# Sheet.net
KiCad netlist of a schematic drawn in Altium Designer
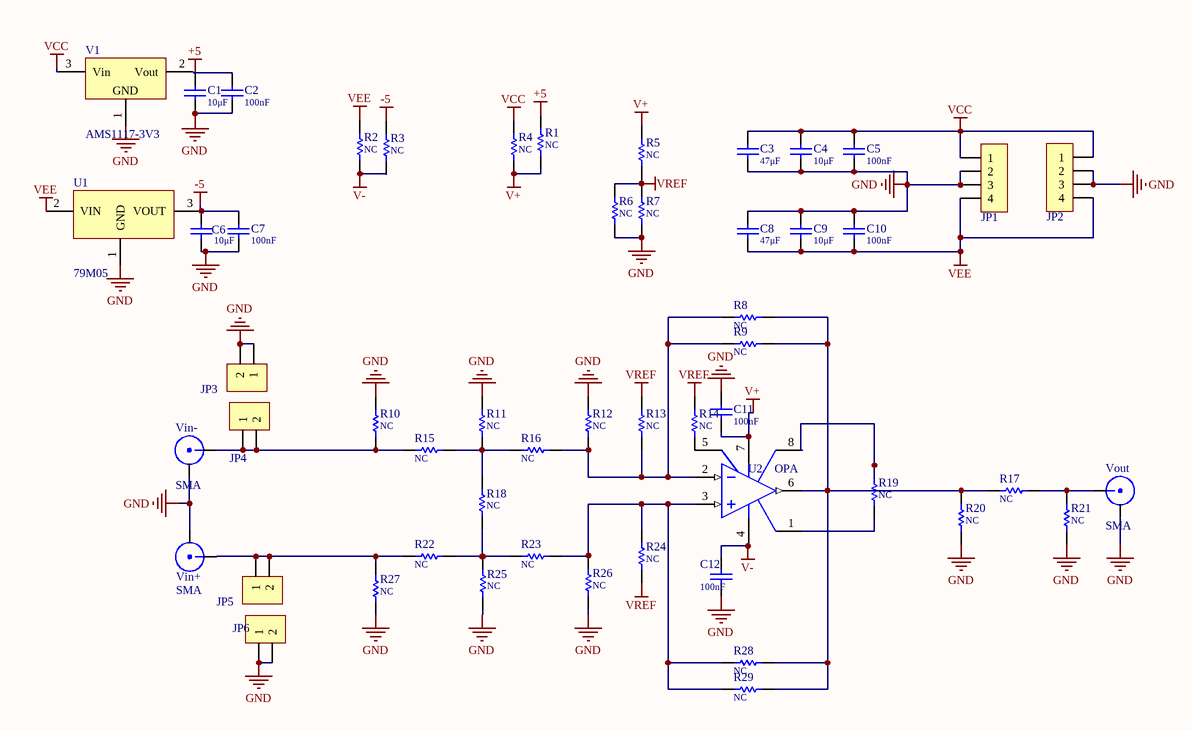
[diagram p0: Sheet.SchDoc]

(export (version "E")
  (design (tool "Eeschema 10.0.6"))
  (components
    (comp (ref "C1")
      (value "10μF")
      (footprint "C0805-L")
      (description "贴片瓷片电容")
      (fields (field (name "Comment") "Cap-S"))
      (libsource (lib "Library") (part "Cap-S"))
    )
    (comp (ref "C2")
      (value "100nF")
      (footprint "C0603-L")
      (description "贴片瓷片电容")
      (fields (field (name "Comment") "Cap-S"))
      (libsource (lib "Library") (part "Cap-S"))
    )
    (comp (ref "C3")
      (value "47μF")
      (footprint "C0805-L")
      (description "贴片瓷片电容")
      (fields (field (name "Comment") "Cap-S"))
      (libsource (lib "Library") (part "Cap-S"))
    )
    (comp (ref "C4")
      (value "10μF")
      (footprint "C0805-L")
      (description "贴片瓷片电容")
      (fields (field (name "Comment") "Cap-S"))
      (libsource (lib "Library") (part "Cap-S"))
    )
    (comp (ref "C5")
      (value "100nF")
      (footprint "C0603-L")
      (description "贴片瓷片电容")
      (fields (field (name "Comment") "Cap-S"))
      (libsource (lib "Library") (part "Cap-S"))
    )
    (comp (ref "C6")
      (value "10μF")
      (footprint "C0805-L")
      (description "贴片瓷片电容")
      (fields (field (name "Comment") "Cap-S"))
      (libsource (lib "Library") (part "Cap-S"))
    )
    (comp (ref "C7")
      (value "100nF")
      (footprint "C0603-L")
      (description "贴片瓷片电容")
      (fields (field (name "Comment") "Cap-S"))
      (libsource (lib "Library") (part "Cap-S"))
    )
    (comp (ref "C8")
      (value "47μF")
      (footprint "C0805-L")
      (description "贴片瓷片电容")
      (fields (field (name "Comment") "Cap-S"))
      (libsource (lib "Library") (part "Cap-S"))
    )
    (comp (ref "C9")
      (value "10μF")
      (footprint "C0805-L")
      (description "贴片瓷片电容")
      (fields (field (name "Comment") "Cap-S"))
      (libsource (lib "Library") (part "Cap-S"))
    )
    (comp (ref "C10")
      (value "100nF")
      (footprint "C0603-L")
      (description "贴片瓷片电容")
      (fields (field (name "Comment") "Cap-S"))
      (libsource (lib "Library") (part "Cap-S"))
    )
    (comp (ref "C11")
      (value "100nF")
      (footprint "C0603-L")
      (description "贴片瓷片电容")
      (fields (field (name "Comment") "Cap-S"))
      (libsource (lib "Library") (part "Cap-S"))
    )
    (comp (ref "C12")
      (value "100nF")
      (footprint "C0603-L")
      (description "贴片瓷片电容")
      (fields (field (name "Comment") "Cap-S"))
      (libsource (lib "Library") (part "Cap-S"))
    )
    (comp (ref "JP1")
      (value "HDR-1X4")
      (footprint "VH3.96-LI-4P")
      (description "4P接插件")
      (fields (field (name "版权归属") "源创客"))
      (libsource (lib "") (part "Header 4_1"))
    )
    (comp (ref "JP2")
      (value "HDR-1X4")
      (footprint "VH3.96-LI-4P")
      (description "4P接插件")
      (fields (field (name "版权归属") "源创客"))
      (libsource (lib "Library1") (part "Header 4"))
    )
    (comp (ref "JP3")
      (value "HDR-1X2")
      (footprint "HDR2.54-LI-2P")
      (description "2P接插件")
      (fields (field (name "版权归属") "源创客"))
      (libsource (lib "IL") (part "Header 2"))
    )
    (comp (ref "JP4")
      (value "HDR-1X2")
      (footprint "HDR2.54-LI-2P")
      (description "2P接插件")
      (fields (field (name "版权归属") "源创客"))
      (libsource (lib "") (part "Header 2_1"))
    )
    (comp (ref "JP5")
      (value "HDR-1X2")
      (footprint "HDR2.54-LI-2P")
      (description "2P接插件")
      (fields (field (name "版权归属") "源创客"))
      (libsource (lib "") (part "Header 2_2"))
    )
    (comp (ref "JP6")
      (value "HDR-1X2")
      (footprint "HDR2.54-LI-2P")
      (description "2P接插件")
      (fields (field (name "版权归属") "源创客"))
      (libsource (lib "") (part "Header 2_1"))
    )
    (comp (ref "R1")
      (value "NC")
      (footprint "R0603-L")
      (description "贴片电阻")
      (fields (field (name "Comment") "R"))
      (libsource (lib "Library") (part "Res"))
    )
    (comp (ref "R2")
      (value "NC")
      (footprint "R0603-L")
      (description "贴片电阻")
      (fields (field (name "Comment") "R"))
      (libsource (lib "Library") (part "Res"))
    )
    (comp (ref "R3")
      (value "NC")
      (footprint "R0603-L")
      (description "贴片电阻")
      (fields (field (name "Comment") "R"))
      (libsource (lib "Library") (part "Res"))
    )
    (comp (ref "R4")
      (value "NC")
      (footprint "R0603-L")
      (description "贴片电阻")
      (fields (field (name "Comment") "R"))
      (libsource (lib "Library") (part "Res"))
    )
    (comp (ref "R5")
      (value "NC")
      (footprint "R0603-L")
      (description "贴片电阻")
      (fields (field (name "Comment") "R"))
      (libsource (lib "Library") (part "Res"))
    )
    (comp (ref "R6")
      (value "NC")
      (footprint "R0603-L")
      (description "贴片电阻")
      (fields (field (name "Comment") "R"))
      (libsource (lib "Library") (part "Res"))
    )
    (comp (ref "R7")
      (value "NC")
      (footprint "R0603-L")
      (description "贴片电阻")
      (fields (field (name "Comment") "R"))
      (libsource (lib "Library") (part "Res"))
    )
    (comp (ref "R8")
      (value "NC")
      (footprint "R0603-L")
      (description "贴片电阻")
      (fields (field (name "Comment") "R"))
      (libsource (lib "Library") (part "Res"))
    )
    (comp (ref "R9")
      (value "NC")
      (footprint "R0603-L")
      (description "贴片电阻")
      (fields (field (name "Comment") "R"))
      (libsource (lib "Library") (part "Res"))
    )
    (comp (ref "R10")
      (value "NC")
      (footprint "R0603-L")
      (description "贴片电阻")
      (fields (field (name "Comment") "R"))
      (libsource (lib "Library") (part "Res"))
    )
    (comp (ref "R11")
      (value "NC")
      (footprint "R0603-L")
      (description "贴片电阻")
      (fields (field (name "Comment") "R"))
      (libsource (lib "Library") (part "Res"))
    )
    (comp (ref "R12")
      (value "NC")
      (footprint "R0603-L")
      (description "贴片电阻")
      (fields (field (name "Comment") "R"))
      (libsource (lib "Library") (part "Res"))
    )
    (comp (ref "R13")
      (value "NC")
      (footprint "R0603-L")
      (description "贴片电阻")
      (fields (field (name "Comment") "R"))
      (libsource (lib "Library") (part "Res"))
    )
    (comp (ref "R14")
      (value "NC")
      (footprint "R0603-L")
      (description "贴片电阻")
      (fields (field (name "Comment") "R"))
      (libsource (lib "Library") (part "Res"))
    )
    (comp (ref "R15")
      (value "NC")
      (footprint "R0603-L")
      (description "贴片电阻")
      (fields (field (name "Comment") "R"))
      (libsource (lib "Library") (part "Res"))
    )
    (comp (ref "R16")
      (value "NC")
      (footprint "R0603-L")
      (description "贴片电阻")
      (fields (field (name "Comment") "R"))
      (libsource (lib "Library") (part "Res"))
    )
    (comp (ref "R17")
      (value "NC")
      (footprint "R0603-L")
      (description "贴片电阻")
      (fields (field (name "Comment") "R"))
      (libsource (lib "Library") (part "Res"))
    )
    (comp (ref "R18")
      (value "NC")
      (footprint "R0603-L")
      (description "贴片电阻")
      (fields (field (name "Comment") "R"))
      (libsource (lib "Library") (part "Res"))
    )
    (comp (ref "R19")
      (value "NC")
      (footprint "R0603-L")
      (description "贴片电阻")
      (fields (field (name "Comment") "R"))
      (libsource (lib "Library") (part "Res"))
    )
    (comp (ref "R20")
      (value "NC")
      (footprint "R0603-L")
      (description "贴片电阻")
      (fields (field (name "Comment") "R"))
      (libsource (lib "Library") (part "Res"))
    )
    (comp (ref "R21")
      (value "NC")
      (footprint "R0603-L")
      (description "贴片电阻")
      (fields (field (name "Comment") "R"))
      (libsource (lib "Library") (part "Res"))
    )
    (comp (ref "R22")
      (value "NC")
      (footprint "R0603-L")
      (description "贴片电阻")
      (fields (field (name "Comment") "R"))
      (libsource (lib "Library") (part "Res"))
    )
    (comp (ref "R23")
      (value "NC")
      (footprint "R0603-L")
      (description "贴片电阻")
      (fields (field (name "Comment") "R"))
      (libsource (lib "Library") (part "Res"))
    )
    (comp (ref "R24")
      (value "NC")
      (footprint "R0603-L")
      (description "贴片电阻")
      (fields (field (name "Comment") "R"))
      (libsource (lib "Library") (part "Res"))
    )
    (comp (ref "R25")
      (value "NC")
      (footprint "R0603-L")
      (description "贴片电阻")
      (fields (field (name "Comment") "R"))
      (libsource (lib "Library") (part "Res"))
    )
    (comp (ref "R26")
      (value "NC")
      (footprint "R0603-L")
      (description "贴片电阻")
      (fields (field (name "Comment") "R"))
      (libsource (lib "Library") (part "Res"))
    )
    (comp (ref "R27")
      (value "NC")
      (footprint "R0603-L")
      (description "贴片电阻")
      (fields (field (name "Comment") "R"))
      (libsource (lib "Library") (part "Res"))
    )
    (comp (ref "R28")
      (value "NC")
      (footprint "R0603-L")
      (description "贴片电阻")
      (fields (field (name "Comment") "R"))
      (libsource (lib "Library") (part "Res"))
    )
    (comp (ref "R29")
      (value "NC")
      (footprint "R0603-L")
      (description "贴片电阻")
      (fields (field (name "Comment") "R"))
      (libsource (lib "Library") (part "Res"))
    )
    (comp (ref "U1")
      (value "79M05")
      (footprint "TO252")
      (description "线性稳压芯片")
      (fields (field (name "版权归属") "源创客"))
      (libsource (lib "IL") (part "79xx"))
    )
    (comp (ref "U2")
      (value "OPA")
      (footprint "SOP8_N")
      (description "双电源高精度运放")
      (fields (field (name "版权归属") "源创客"))
      (libsource (lib "Library1") (part "OPA277"))
    )
    (comp (ref "V1")
      (value "AMS1117-3V3")
      (footprint "SOT223_L")
      (description "三端稳压芯片")
      (fields (field (name "版权归属") "源创客"))
      (libsource (lib "IL") (part "AMS1117"))
    )
    (comp (ref "Vin+") (value "SMA") (footprint "SMA1") (libsource (lib "Library") (part "SMA")))
    (comp (ref "Vin-") (value "SMA") (footprint "SMA1") (libsource (lib "") (part "SMA_1")))
    (comp (ref "Vout") (value "SMA") (footprint "SMA1") (libsource (lib "Library") (part "SMA")))
  )
  (nets
    (net (code "1") (name "+5") (class "Default")
      (node (ref "C1") (pin "2") (pinfunction "2_2") (pintype "passive"))
      (node (ref "C2") (pin "2") (pinfunction "2_2") (pintype "passive"))
      (node (ref "R1") (pin "1") (pinfunction "1_1") (pintype "passive"))
      (node (ref "V1") (pin "2") (pinfunction "Vout_2") (pintype "passive"))
    )
    (net (code "2") (name "-5") (class "Default")
      (node (ref "C6") (pin "2") (pinfunction "2_2") (pintype "passive"))
      (node (ref "C7") (pin "2") (pinfunction "2_2") (pintype "passive"))
      (node (ref "R3") (pin "1") (pinfunction "1_1") (pintype "passive"))
      (node (ref "U1") (pin "3") (pinfunction "VOUT_3") (pintype "passive"))
    )
    (net (code "3") (name "GND") (class "Default")
      (node (ref "C1") (pin "1") (pinfunction "1_1") (pintype "passive"))
      (node (ref "C10") (pin "2") (pinfunction "2_2") (pintype "passive"))
      (node (ref "C11") (pin "2") (pinfunction "2_2") (pintype "passive"))
      (node (ref "C12") (pin "1") (pinfunction "1_1") (pintype "passive"))
      (node (ref "C2") (pin "1") (pinfunction "1_1") (pintype "passive"))
      (node (ref "C3") (pin "1") (pinfunction "1_1") (pintype "passive"))
      (node (ref "C4") (pin "1") (pinfunction "1_1") (pintype "passive"))
      (node (ref "C5") (pin "1") (pinfunction "1_1") (pintype "passive"))
      (node (ref "C6") (pin "1") (pinfunction "1_1") (pintype "passive"))
      (node (ref "C7") (pin "1") (pinfunction "1_1") (pintype "passive"))
      (node (ref "C8") (pin "2") (pinfunction "2_2") (pintype "passive"))
      (node (ref "C9") (pin "2") (pinfunction "2_2") (pintype "passive"))
      (node (ref "JP1") (pin "2") (pinfunction "2_2") (pintype "passive"))
      (node (ref "JP1") (pin "3") (pinfunction "3_3") (pintype "passive"))
      (node (ref "JP2") (pin "2") (pinfunction "2_2") (pintype "passive"))
      (node (ref "JP2") (pin "3") (pinfunction "3_3") (pintype "passive"))
      (node (ref "JP3") (pin "1") (pinfunction "1_1") (pintype "passive"))
      (node (ref "JP3") (pin "2") (pinfunction "2_2") (pintype "passive"))
      (node (ref "JP6") (pin "1") (pinfunction "1_1") (pintype "passive"))
      (node (ref "JP6") (pin "2") (pinfunction "2_2") (pintype "passive"))
      (node (ref "R10") (pin "2") (pinfunction "2_2") (pintype "passive"))
      (node (ref "R11") (pin "2") (pinfunction "2_2") (pintype "passive"))
      (node (ref "R12") (pin "2") (pinfunction "2_2") (pintype "passive"))
      (node (ref "R20") (pin "1") (pinfunction "1_1") (pintype "passive"))
      (node (ref "R21") (pin "1") (pinfunction "1_1") (pintype "passive"))
      (node (ref "R25") (pin "1") (pinfunction "1_1") (pintype "passive"))
      (node (ref "R26") (pin "1") (pinfunction "1_1") (pintype "passive"))
      (node (ref "R27") (pin "1") (pinfunction "1_1") (pintype "passive"))
      (node (ref "R6") (pin "2") (pinfunction "2_2") (pintype "passive"))
      (node (ref "R7") (pin "2") (pinfunction "2_2") (pintype "passive"))
      (node (ref "U1") (pin "1") (pinfunction "GND_1") (pintype "passive"))
      (node (ref "V1") (pin "1") (pinfunction "GND_1") (pintype "passive"))
      (node (ref "Vin+") (pin "2") (pinfunction "2_2") (pintype "passive"))
      (node (ref "Vin-") (pin "2") (pinfunction "2_2") (pintype "passive"))
      (node (ref "Vout") (pin "2") (pinfunction "2_2") (pintype "passive"))
    )
    (net (code "4") (name "Net-(JP4-Pad1)") (class "Default")
      (node (ref "JP4") (pin "1") (pinfunction "1_1") (pintype "passive"))
      (node (ref "JP4") (pin "2") (pinfunction "2_2") (pintype "passive"))
      (node (ref "R10") (pin "1") (pinfunction "1_1") (pintype "passive"))
      (node (ref "R15") (pin "1") (pinfunction "1_1") (pintype "passive"))
      (node (ref "Vin-") (pin "1") (pinfunction "1_1") (pintype "passive"))
    )
    (net (code "5") (name "Net-(JP5-Pad1)") (class "Default")
      (node (ref "JP5") (pin "1") (pinfunction "1_1") (pintype "passive"))
      (node (ref "JP5") (pin "2") (pinfunction "2_2") (pintype "passive"))
      (node (ref "R22") (pin "1") (pinfunction "1_1") (pintype "passive"))
      (node (ref "R27") (pin "2") (pinfunction "2_2") (pintype "passive"))
      (node (ref "Vin+") (pin "1") (pinfunction "1_1") (pintype "passive"))
    )
    (net (code "6") (name "Net-(R11-Pad1)") (class "Default")
      (node (ref "R11") (pin "1") (pinfunction "1_1") (pintype "passive"))
      (node (ref "R15") (pin "2") (pinfunction "2_2") (pintype "passive"))
      (node (ref "R16") (pin "1") (pinfunction "1_1") (pintype "passive"))
      (node (ref "R18") (pin "1") (pinfunction "1_1") (pintype "passive"))
    )
    (net (code "7") (name "Net-(R17-Pad2)") (class "Default")
      (node (ref "R17") (pin "2") (pinfunction "2_2") (pintype "passive"))
      (node (ref "R21") (pin "2") (pinfunction "2_2") (pintype "passive"))
      (node (ref "Vout") (pin "1") (pinfunction "1_1") (pintype "passive"))
    )
    (net (code "8") (name "Net-(R18-Pad2)") (class "Default")
      (node (ref "R18") (pin "2") (pinfunction "2_2") (pintype "passive"))
      (node (ref "R22") (pin "2") (pinfunction "2_2") (pintype "passive"))
      (node (ref "R23") (pin "1") (pinfunction "1_1") (pintype "passive"))
      (node (ref "R25") (pin "2") (pinfunction "2_2") (pintype "passive"))
    )
    (net (code "9") (name "Net-(R19-Pad1)") (class "Default")
      (node (ref "R19") (pin "1") (pinfunction "1_1") (pintype "passive"))
      (node (ref "U2") (pin "8") (pinfunction "8_8") (pintype "passive"))
    )
    (net (code "10") (name "Net-(R19-Pad2)") (class "Default")
      (node (ref "R19") (pin "2") (pinfunction "2_2") (pintype "passive"))
      (node (ref "U2") (pin "1") (pinfunction "1_1") (pintype "passive"))
    )
    (net (code "11") (name "Net-(U2-IN+)") (class "Default")
      (node (ref "R23") (pin "2") (pinfunction "2_2") (pintype "passive"))
      (node (ref "R24") (pin "2") (pinfunction "2_2") (pintype "passive"))
      (node (ref "R26") (pin "2") (pinfunction "2_2") (pintype "passive"))
      (node (ref "R28") (pin "1") (pinfunction "1_1") (pintype "passive"))
      (node (ref "R29") (pin "1") (pinfunction "1_1") (pintype "passive"))
      (node (ref "U2") (pin "3") (pinfunction "IN+_3") (pintype "input"))
    )
    (net (code "12") (name "Net-(U2-IN-)") (class "Default")
      (node (ref "R12") (pin "1") (pinfunction "1_1") (pintype "passive"))
      (node (ref "R13") (pin "1") (pinfunction "1_1") (pintype "passive"))
      (node (ref "R16") (pin "2") (pinfunction "2_2") (pintype "passive"))
      (node (ref "R8") (pin "1") (pinfunction "1_1") (pintype "passive"))
      (node (ref "R9") (pin "1") (pinfunction "1_1") (pintype "passive"))
      (node (ref "U2") (pin "2") (pinfunction "IN-_2") (pintype "input"))
    )
    (net (code "13") (name "Net-(U2-NC)") (class "Default")
      (node (ref "R14") (pin "1") (pinfunction "1_1") (pintype "passive"))
      (node (ref "U2") (pin "5") (pinfunction "NC_5") (pintype "power_in"))
    )
    (net (code "14") (name "Net-(U2-OS_NUL)") (class "Default")
      (node (ref "R17") (pin "1") (pinfunction "1_1") (pintype "passive"))
      (node (ref "R20") (pin "2") (pinfunction "2_2") (pintype "passive"))
      (node (ref "R28") (pin "2") (pinfunction "2_2") (pintype "passive"))
      (node (ref "R29") (pin "2") (pinfunction "2_2") (pintype "passive"))
      (node (ref "R8") (pin "2") (pinfunction "2_2") (pintype "passive"))
      (node (ref "R9") (pin "2") (pinfunction "2_2") (pintype "passive"))
      (node (ref "U2") (pin "6") (pinfunction "OS_NUL_6") (pintype "output"))
    )
    (net (code "15") (name "V+") (class "Default")
      (node (ref "C11") (pin "1") (pinfunction "1_1") (pintype "passive"))
      (node (ref "R1") (pin "2") (pinfunction "2_2") (pintype "passive"))
      (node (ref "R4") (pin "2") (pinfunction "2_2") (pintype "passive"))
      (node (ref "R5") (pin "1") (pinfunction "1_1") (pintype "passive"))
      (node (ref "U2") (pin "7") (pinfunction "7_7") (pintype "passive"))
    )
    (net (code "16") (name "V-") (class "Default")
      (node (ref "C12") (pin "2") (pinfunction "2_2") (pintype "passive"))
      (node (ref "R2") (pin "2") (pinfunction "2_2") (pintype "passive"))
      (node (ref "R3") (pin "2") (pinfunction "2_2") (pintype "passive"))
      (node (ref "U2") (pin "4") (pinfunction "V-_4") (pintype "power_in"))
    )
    (net (code "17") (name "VCC") (class "Default")
      (node (ref "C3") (pin "2") (pinfunction "2_2") (pintype "passive"))
      (node (ref "C4") (pin "2") (pinfunction "2_2") (pintype "passive"))
      (node (ref "C5") (pin "2") (pinfunction "2_2") (pintype "passive"))
      (node (ref "JP1") (pin "1") (pinfunction "1_1") (pintype "passive"))
      (node (ref "JP2") (pin "1") (pinfunction "1_1") (pintype "passive"))
      (node (ref "R4") (pin "1") (pinfunction "1_1") (pintype "passive"))
      (node (ref "V1") (pin "3") (pinfunction "Vin_3") (pintype "passive"))
    )
    (net (code "18") (name "VEE") (class "Default")
      (node (ref "C10") (pin "1") (pinfunction "1_1") (pintype "passive"))
      (node (ref "C8") (pin "1") (pinfunction "1_1") (pintype "passive"))
      (node (ref "C9") (pin "1") (pinfunction "1_1") (pintype "passive"))
      (node (ref "JP1") (pin "4") (pinfunction "4_4") (pintype "passive"))
      (node (ref "JP2") (pin "4") (pinfunction "4_4") (pintype "passive"))
      (node (ref "R2") (pin "1") (pinfunction "1_1") (pintype "passive"))
      (node (ref "U1") (pin "2") (pinfunction "VIN_2") (pintype "passive"))
    )
    (net (code "19") (name "VREF") (class "Default")
      (node (ref "R13") (pin "2") (pinfunction "2_2") (pintype "passive"))
      (node (ref "R14") (pin "2") (pinfunction "2_2") (pintype "passive"))
      (node (ref "R24") (pin "1") (pinfunction "1_1") (pintype "passive"))
      (node (ref "R5") (pin "2") (pinfunction "2_2") (pintype "passive"))
      (node (ref "R6") (pin "1") (pinfunction "1_1") (pintype "passive"))
      (node (ref "R7") (pin "1") (pinfunction "1_1") (pintype "passive"))
    )
  )
)
